# Fuente3_3VDC.net
KiCad netlist of a schematic drawn in Altium Designer
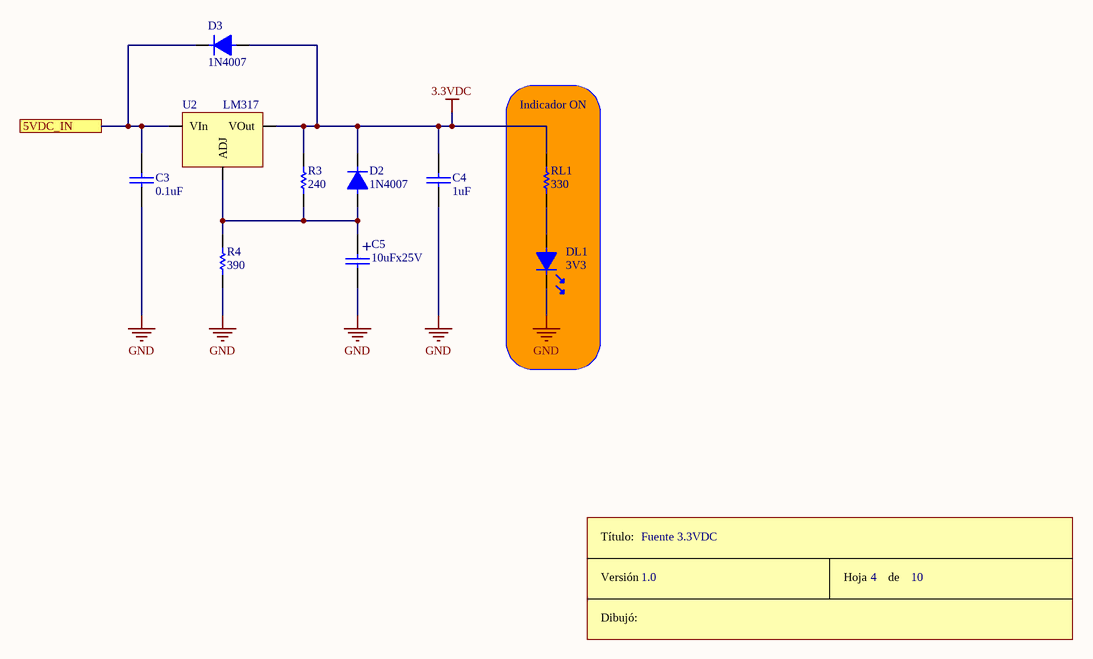
[diagram p0: Fuente3.3VDC.SchDoc]

(export (version "E")
  (design (tool "Eeschema 10.0.6"))
  (components
    (comp (ref "C3") (value "0.1uF") (footprint "CAP100") (libsource (lib "LIBEBAL") (part "CAP")))
    (comp (ref "C4") (value "1uF") (footprint "CAP200") (libsource (lib "LIBEBAL") (part "CAP")))
    (comp (ref "C5") (value "10uFx25V") (footprint "CAP100RP") (libsource (lib "LIBEBAL") (part "CAPPOL")))
    (comp (ref "D2") (value "1N4007") (footprint "DO41") (libsource (lib "LIBEBAL") (part "DIODO")))
    (comp (ref "D3") (value "1N4007") (footprint "DO41") (libsource (lib "LIBEBAL") (part "DIODO")))
    (comp (ref "DL1") (value "3V3") (footprint "LED3") (libsource (lib "LIBEBAL") (part "LED")))
    (comp (ref "R3") (value "240") (footprint "RES400") (libsource (lib "LIBEBAL") (part "RES")))
    (comp (ref "R4") (value "390") (footprint "RES400") (libsource (lib "LIBEBAL") (part "RES")))
    (comp (ref "RL1") (value "330") (footprint "RES300") (libsource (lib "LIBEBAL") (part "RES")))
    (comp (ref "ROT2") (value "Rótulo") (libsource (lib "LIB PIO IX") (part "Rótulo")))
    (comp (ref "U2")
      (value "LM317")
      (footprint "TO-220 H")
      (description "IC REG ADJ 1.5A 3 TERM TO-220")
      (libsource (lib "LIBEBAL") (part "LM317"))
    )
  )
  (nets
    (net (code "1") (name "/5VDC_IN") (class "Default")
      (node (ref "C3") (pin "1") (pinfunction "1_1") (pintype "passive"))
      (node (ref "D3") (pin "2") (pinfunction "2_2") (pintype "passive"))
      (node (ref "U2") (pin "3") (pinfunction "VIn_3") (pintype "passive"))
    )
    (net (code "2") (name "3.3VDC") (class "Default")
      (node (ref "C4") (pin "1") (pinfunction "1_1") (pintype "passive"))
      (node (ref "D2") (pin "2") (pinfunction "2_2") (pintype "passive"))
      (node (ref "D3") (pin "1") (pinfunction "1_1") (pintype "passive"))
      (node (ref "R3") (pin "2") (pinfunction "2_2") (pintype "passive"))
      (node (ref "RL1") (pin "2") (pinfunction "2_2") (pintype "passive"))
      (node (ref "U2") (pin "2") (pinfunction "VOut_2") (pintype "passive"))
    )
    (net (code "3") (name "GND") (class "Default")
      (node (ref "C3") (pin "2") (pinfunction "2_2") (pintype "passive"))
      (node (ref "C4") (pin "2") (pinfunction "2_2") (pintype "passive"))
      (node (ref "C5") (pin "2") (pinfunction "2_2") (pintype "passive"))
      (node (ref "DL1") (pin "2") (pinfunction "2_2") (pintype "passive"))
      (node (ref "R4") (pin "1") (pinfunction "1_1") (pintype "passive"))
    )
    (net (code "4") (name "Net-(DL1-Pad1)") (class "Default")
      (node (ref "DL1") (pin "1") (pinfunction "1_1") (pintype "passive"))
      (node (ref "RL1") (pin "1") (pinfunction "1_1") (pintype "passive"))
    )
    (net (code "5") (name "Net-(U2-ADJ)") (class "Default")
      (node (ref "C5") (pin "1") (pinfunction "1_1") (pintype "passive"))
      (node (ref "D2") (pin "1") (pinfunction "1_1") (pintype "passive"))
      (node (ref "R3") (pin "1") (pinfunction "1_1") (pintype "passive"))
      (node (ref "R4") (pin "2") (pinfunction "2_2") (pintype "passive"))
      (node (ref "U2") (pin "1") (pinfunction "ADJ_1") (pintype "passive"))
    )
  )
)
